# Current_Sense.net
KiCad netlist of a schematic drawn in Altium Designer
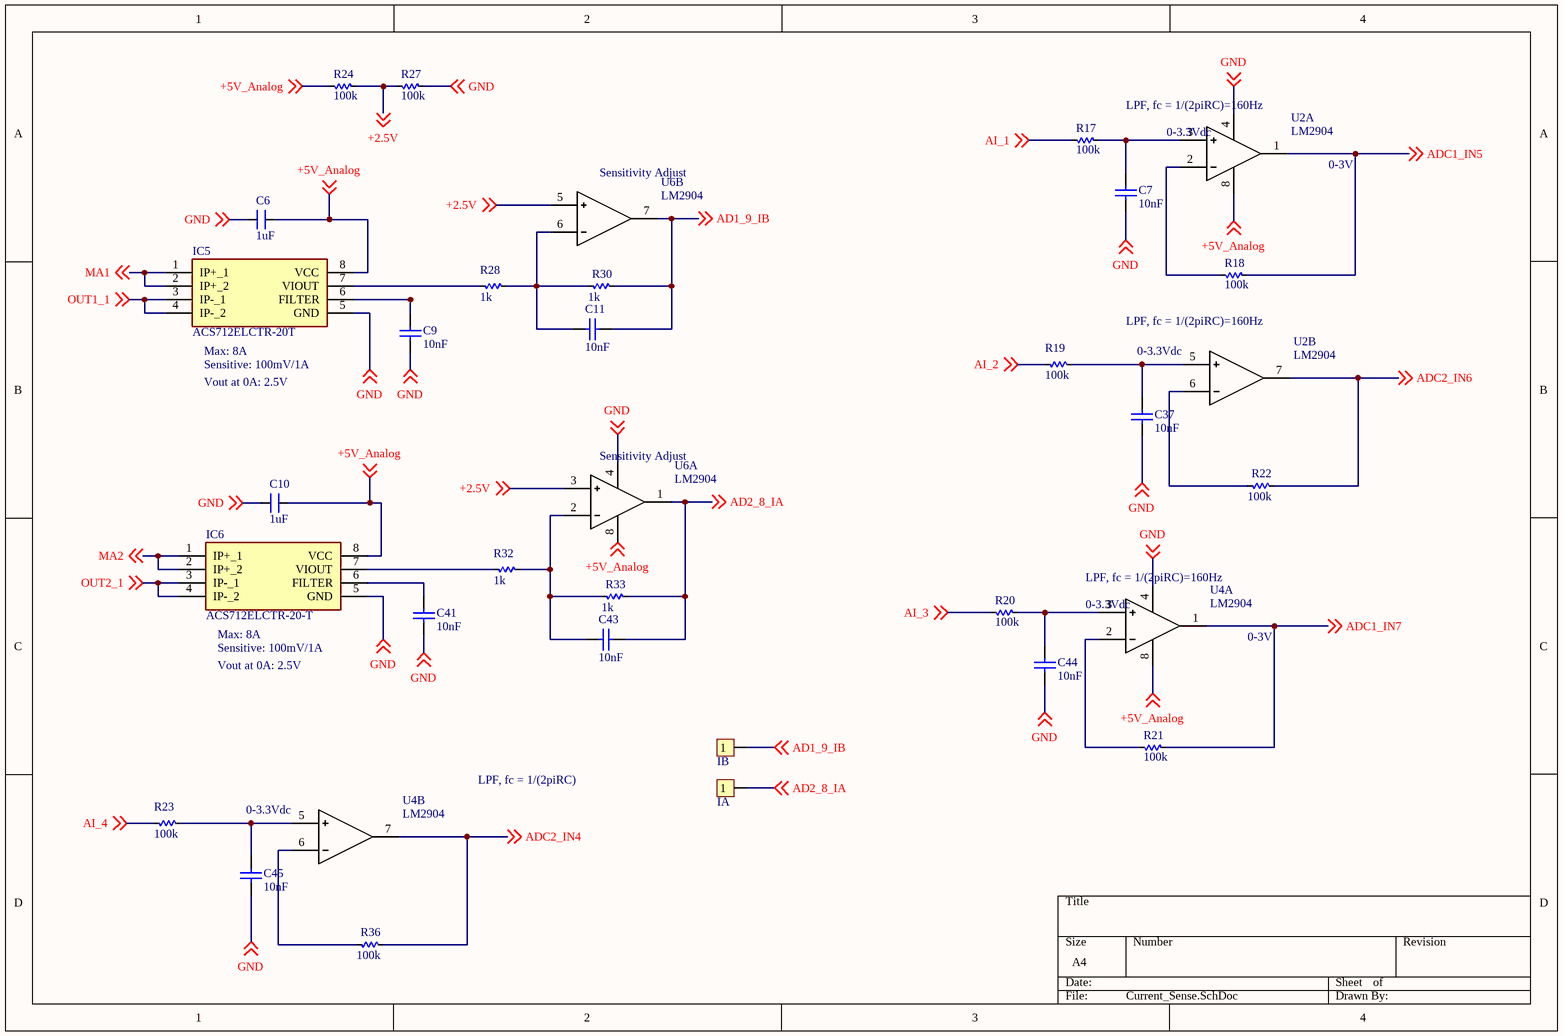
[diagram p0: Current_Sense.SchDoc]

(export (version "E")
  (design (tool "Eeschema 10.0.6"))
  (components
    (comp (ref "C6")
      (value "1uF")
      (footprint "Arduino_PLC_PCB:CM-0805 capacitor")
      (description "0805_SMD_20pF")
      (libsource (lib "Arduino_PLC_SchLib") (part "CN"))
    )
    (comp (ref "C7")
      (value "10nF")
      (footprint "tu 0603")
      (description "Dán")
      (libsource (lib "Tu dien") (part "Tu 0603 102 50V 10%"))
    )
    (comp (ref "C9")
      (value "10nF")
      (footprint "tu 0603")
      (description "Dán")
      (libsource (lib "Tu dien") (part "Tu 0603 102 50V 10%"))
    )
    (comp (ref "C10")
      (value "1uF")
      (footprint "Arduino_PLC_PCB:CM-0805 capacitor")
      (description "0805_SMD_20pF")
      (libsource (lib "Arduino_PLC_SchLib") (part "CN"))
    )
    (comp (ref "C11")
      (value "10nF")
      (footprint "tu 0603")
      (description "Dán")
      (libsource (lib "Tu dien") (part "Tu 0603 102 50V 10%"))
    )
    (comp (ref "C37")
      (value "10nF")
      (footprint "tu 0603")
      (description "Dán")
      (libsource (lib "Tu dien") (part "Tu 0603 102 50V 10%"))
    )
    (comp (ref "C41")
      (value "10nF")
      (footprint "tu 0603")
      (description "Dán")
      (libsource (lib "Tu dien") (part "Tu 0603 102 50V 10%"))
    )
    (comp (ref "C43")
      (value "10nF")
      (footprint "tu 0603")
      (description "Dán")
      (libsource (lib "Tu dien") (part "Tu 0603 102 50V 10%"))
    )
    (comp (ref "C44")
      (value "10nF")
      (footprint "tu 0603")
      (description "Dán")
      (libsource (lib "Tu dien") (part "Tu 0603 102 50V 10%"))
    )
    (comp (ref "C45")
      (value "10nF")
      (footprint "tu 0603")
      (description "Dán")
      (libsource (lib "Tu dien") (part "Tu 0603 102 50V 10%"))
    )
    (comp (ref "IA")
      (value "IA")
      (footprint "JP 1x1 DT")
      (description "Cắm")
      (libsource (lib "Jump") (part "JP 1x1 2.54 Duc Cong"))
    )
    (comp (ref "IB")
      (value "IB")
      (footprint "JP 1x1 DT")
      (description "Cắm")
      (libsource (lib "Jump") (part "JP 1x1 2.54 Duc Cong"))
    )
    (comp (ref "IC5")
      (value "ACS712ELCTR-20T")
      (footprint "SO8")
      (description "Integrated Circuit")
      (fields (field (name "MANUFACTURER_PART_NUMBER") "ACS712ELCTR-20A-T"))
      (libsource (lib "*") (part "ACS712ELCTR-20A-T"))
    )
    (comp (ref "IC6")
      (value "ACS712ELCTR-20-T")
      (footprint "SO8")
      (description "Integrated Circuit")
      (fields (field (name "MANUFACTURER_PART_NUMBER") "ACS712ELCTR-20A-T"))
      (libsource (lib "*") (part "ACS712ELCTR-20A-T"))
    )
    (comp (ref "R17")
      (value "100k")
      (footprint "RES-SMD-0603")
      (description "Resistor")
      (fields
        (field (name "MANUFACTURER") "Generic Components")
        (field (name "PUBLISHER") "Altium Hobart Technology Centre")
      )
      (libsource (lib "LIBRARY") (part "Res-SMD"))
    )
    (comp (ref "R18")
      (value "100k")
      (footprint "RES-SMD-0603")
      (description "Resistor")
      (fields
        (field (name "MANUFACTURER") "Generic Components")
        (field (name "PUBLISHER") "Altium Hobart Technology Centre")
      )
      (libsource (lib "LIBRARY") (part "Res-SMD"))
    )
    (comp (ref "R19")
      (value "100k")
      (footprint "RES-SMD-0603")
      (description "Resistor")
      (fields
        (field (name "MANUFACTURER") "Generic Components")
        (field (name "PUBLISHER") "Altium Hobart Technology Centre")
      )
      (libsource (lib "LIBRARY") (part "Res-SMD"))
    )
    (comp (ref "R20")
      (value "100k")
      (footprint "RES-SMD-0603")
      (description "Resistor")
      (fields
        (field (name "MANUFACTURER") "Generic Components")
        (field (name "PUBLISHER") "Altium Hobart Technology Centre")
      )
      (libsource (lib "LIBRARY") (part "Res-SMD"))
    )
    (comp (ref "R21")
      (value "100k")
      (footprint "RES-SMD-0603")
      (description "Resistor")
      (fields
        (field (name "MANUFACTURER") "Generic Components")
        (field (name "PUBLISHER") "Altium Hobart Technology Centre")
      )
      (libsource (lib "LIBRARY") (part "Res-SMD"))
    )
    (comp (ref "R22")
      (value "100k")
      (footprint "RES-SMD-0603")
      (description "Resistor")
      (fields
        (field (name "MANUFACTURER") "Generic Components")
        (field (name "PUBLISHER") "Altium Hobart Technology Centre")
      )
      (libsource (lib "LIBRARY") (part "Res-SMD"))
    )
    (comp (ref "R23")
      (value "100k")
      (footprint "RES-SMD-0603")
      (description "Resistor")
      (fields
        (field (name "MANUFACTURER") "Generic Components")
        (field (name "PUBLISHER") "Altium Hobart Technology Centre")
      )
      (libsource (lib "LIBRARY") (part "Res-SMD"))
    )
    (comp (ref "R24")
      (value "100k")
      (footprint "RES-SMD-0603")
      (description "Resistor")
      (fields
        (field (name "MANUFACTURER") "Generic Components")
        (field (name "PUBLISHER") "Altium Hobart Technology Centre")
      )
      (libsource (lib "LIBRARY") (part "Res-SMD"))
    )
    (comp (ref "R27")
      (value "100k")
      (footprint "RES-SMD-0603")
      (description "Resistor")
      (fields
        (field (name "MANUFACTURER") "Generic Components")
        (field (name "PUBLISHER") "Altium Hobart Technology Centre")
      )
      (libsource (lib "LIBRARY") (part "Res-SMD"))
    )
    (comp (ref "R28")
      (value "1k")
      (footprint "RES-SMD-0603")
      (description "Resistor")
      (fields
        (field (name "MANUFACTURER") "Generic Components")
        (field (name "PUBLISHER") "Altium Hobart Technology Centre")
      )
      (libsource (lib "LIBRARY") (part "Res-SMD"))
    )
    (comp (ref "R30")
      (value "1k")
      (footprint "RES-SMD-0603")
      (description "Resistor")
      (fields
        (field (name "MANUFACTURER") "Generic Components")
        (field (name "PUBLISHER") "Altium Hobart Technology Centre")
      )
      (libsource (lib "LIBRARY") (part "Res-SMD"))
    )
    (comp (ref "R32")
      (value "1k")
      (footprint "RES-SMD-0603")
      (description "Resistor")
      (fields
        (field (name "MANUFACTURER") "Generic Components")
        (field (name "PUBLISHER") "Altium Hobart Technology Centre")
      )
      (libsource (lib "LIBRARY") (part "Res-SMD"))
    )
    (comp (ref "R33")
      (value "1k")
      (footprint "RES-SMD-0603")
      (description "Resistor")
      (fields
        (field (name "MANUFACTURER") "Generic Components")
        (field (name "PUBLISHER") "Altium Hobart Technology Centre")
      )
      (libsource (lib "LIBRARY") (part "Res-SMD"))
    )
    (comp (ref "R36")
      (value "100k")
      (footprint "RES-SMD-0603")
      (description "Resistor")
      (fields
        (field (name "MANUFACTURER") "Generic Components")
        (field (name "PUBLISHER") "Altium Hobart Technology Centre")
      )
      (libsource (lib "LIBRARY") (part "Res-SMD"))
    )
    (comp (ref "U2")
      (value "LM2904")
      (footprint "SO8")
      (description "IC DUAL COMPARATOR")
      (libsource (lib "LIBRARY") (part "LM393-SPLIT"))
    )
    (comp (ref "U4")
      (value "LM2904")
      (footprint "SO8")
      (description "IC DUAL COMPARATOR")
      (libsource (lib "LIBRARY") (part "LM393-SPLIT"))
    )
    (comp (ref "U6")
      (value "LM2904")
      (footprint "SO8")
      (description "IC DUAL COMPARATOR")
      (libsource (lib "LIBRARY") (part "LM393-SPLIT"))
    )
  )
  (nets
    (net (code "1") (name "+2.5V") (class "Default")
      (node (ref "R24") (pin "1") (pinfunction "1_1") (pintype "passive"))
      (node (ref "R27") (pin "2") (pinfunction "2_2") (pintype "passive"))
      (node (ref "U6") (pin "3") (pintype "passive"))
      (node (ref "U6") (pin "5") (pintype "passive"))
    )
    (net (code "2") (name "+5V_Analog") (class "Default")
      (node (ref "C10") (pin "1") (pinfunction "1_1") (pintype "passive"))
      (node (ref "C6") (pin "1") (pinfunction "1_1") (pintype "passive"))
      (node (ref "IC5") (pin "8") (pinfunction "VCC_8") (pintype "passive"))
      (node (ref "IC6") (pin "8") (pinfunction "VCC_8") (pintype "passive"))
      (node (ref "R24") (pin "2") (pinfunction "2_2") (pintype "passive"))
      (node (ref "U2") (pin "8") (pinfunction "Vcc+_8") (pintype "passive"))
      (node (ref "U4") (pin "8") (pinfunction "Vcc+_8") (pintype "passive"))
      (node (ref "U6") (pin "8") (pinfunction "Vcc+_8") (pintype "passive"))
    )
    (net (code "3") (name "AD1_9_IB") (class "Default")
      (node (ref "C11") (pin "2") (pinfunction "2_2") (pintype "passive"))
      (node (ref "IB") (pin "1") (pinfunction "1_1") (pintype "passive"))
      (node (ref "R30") (pin "1") (pinfunction "1_1") (pintype "passive"))
      (node (ref "U6") (pin "7") (pintype "passive"))
    )
    (net (code "4") (name "AD2_8_IA") (class "Default")
      (node (ref "C43") (pin "2") (pinfunction "2_2") (pintype "passive"))
      (node (ref "IA") (pin "1") (pinfunction "1_1") (pintype "passive"))
      (node (ref "R33") (pin "1") (pinfunction "1_1") (pintype "passive"))
      (node (ref "U6") (pin "1") (pintype "passive"))
    )
    (net (code "5") (name "ADC1_IN5") (class "Default")
      (node (ref "R18") (pin "2") (pinfunction "2_2") (pintype "passive"))
      (node (ref "U2") (pin "1") (pintype "passive"))
    )
    (net (code "6") (name "ADC1_IN7") (class "Default")
      (node (ref "R21") (pin "2") (pinfunction "2_2") (pintype "passive"))
      (node (ref "U4") (pin "1") (pintype "passive"))
    )
    (net (code "7") (name "ADC2_IN4") (class "Default")
      (node (ref "R36") (pin "1") (pinfunction "1_1") (pintype "passive"))
      (node (ref "U4") (pin "7") (pintype "passive"))
    )
    (net (code "8") (name "ADC2_IN6") (class "Default")
      (node (ref "R22") (pin "1") (pinfunction "1_1") (pintype "passive"))
      (node (ref "U2") (pin "7") (pintype "passive"))
    )
    (net (code "9") (name "AI_1") (class "Default")
      (node (ref "R17") (pin "2") (pinfunction "2_2") (pintype "passive"))
    )
    (net (code "10") (name "AI_2") (class "Default")
      (node (ref "R19") (pin "1") (pinfunction "1_1") (pintype "passive"))
    )
    (net (code "11") (name "AI_3") (class "Default")
      (node (ref "R20") (pin "2") (pinfunction "2_2") (pintype "passive"))
    )
    (net (code "12") (name "AI_4") (class "Default")
      (node (ref "R23") (pin "1") (pinfunction "1_1") (pintype "passive"))
    )
    (net (code "13") (name "GND") (class "Default")
      (node (ref "C10") (pin "2") (pinfunction "2_2") (pintype "passive"))
      (node (ref "C37") (pin "2") (pinfunction "2_2") (pintype "passive"))
      (node (ref "C41") (pin "1") (pinfunction "1_1") (pintype "passive"))
      (node (ref "C44") (pin "1") (pinfunction "1_1") (pintype "passive"))
      (node (ref "C45") (pin "2") (pinfunction "2_2") (pintype "passive"))
      (node (ref "C6") (pin "2") (pinfunction "2_2") (pintype "passive"))
      (node (ref "C7") (pin "2") (pinfunction "2_2") (pintype "passive"))
      (node (ref "C9") (pin "2") (pinfunction "2_2") (pintype "passive"))
      (node (ref "IC5") (pin "5") (pinfunction "GND_5") (pintype "passive"))
      (node (ref "IC6") (pin "5") (pinfunction "GND_5") (pintype "passive"))
      (node (ref "R27") (pin "1") (pinfunction "1_1") (pintype "passive"))
      (node (ref "U2") (pin "4") (pinfunction "Vcc-_4") (pintype "passive"))
      (node (ref "U4") (pin "4") (pinfunction "Vcc-_4") (pintype "passive"))
      (node (ref "U6") (pin "4") (pinfunction "Vcc-_4") (pintype "passive"))
    )
    (net (code "14") (name "MA1") (class "Default")
      (node (ref "IC5") (pin "1") (pinfunction "IP+_1_1") (pintype "passive"))
      (node (ref "IC5") (pin "2") (pinfunction "IP+_2_2") (pintype "passive"))
    )
    (net (code "15") (name "MA2") (class "Default")
      (node (ref "IC6") (pin "1") (pinfunction "IP+_1_1") (pintype "passive"))
      (node (ref "IC6") (pin "2") (pinfunction "IP+_2_2") (pintype "passive"))
    )
    (net (code "16") (name "Net-(C7-Pad1)") (class "Default")
      (node (ref "C7") (pin "1") (pinfunction "1_1") (pintype "passive"))
      (node (ref "R17") (pin "1") (pinfunction "1_1") (pintype "passive"))
      (node (ref "U2") (pin "3") (pintype "passive"))
    )
    (net (code "17") (name "Net-(C11-Pad1)") (class "Default")
      (node (ref "C11") (pin "1") (pinfunction "1_1") (pintype "passive"))
      (node (ref "R28") (pin "2") (pinfunction "2_2") (pintype "passive"))
      (node (ref "R30") (pin "2") (pinfunction "2_2") (pintype "passive"))
      (node (ref "U6") (pin "6") (pintype "passive"))
    )
    (net (code "18") (name "Net-(C37-Pad1)") (class "Default")
      (node (ref "C37") (pin "1") (pinfunction "1_1") (pintype "passive"))
      (node (ref "R19") (pin "2") (pinfunction "2_2") (pintype "passive"))
      (node (ref "U2") (pin "5") (pintype "passive"))
    )
    (net (code "19") (name "Net-(C43-Pad1)") (class "Default")
      (node (ref "C43") (pin "1") (pinfunction "1_1") (pintype "passive"))
      (node (ref "R32") (pin "2") (pinfunction "2_2") (pintype "passive"))
      (node (ref "R33") (pin "2") (pinfunction "2_2") (pintype "passive"))
      (node (ref "U6") (pin "2") (pintype "passive"))
    )
    (net (code "20") (name "Net-(C44-Pad2)") (class "Default")
      (node (ref "C44") (pin "2") (pinfunction "2_2") (pintype "passive"))
      (node (ref "R20") (pin "1") (pinfunction "1_1") (pintype "passive"))
      (node (ref "U4") (pin "3") (pintype "passive"))
    )
    (net (code "21") (name "Net-(C45-Pad1)") (class "Default")
      (node (ref "C45") (pin "1") (pinfunction "1_1") (pintype "passive"))
      (node (ref "R23") (pin "2") (pinfunction "2_2") (pintype "passive"))
      (node (ref "U4") (pin "5") (pintype "passive"))
    )
    (net (code "22") (name "Net-(IC5-FILTER)") (class "Default")
      (node (ref "C9") (pin "1") (pinfunction "1_1") (pintype "passive"))
      (node (ref "IC5") (pin "6") (pinfunction "FILTER_6") (pintype "passive"))
    )
    (net (code "23") (name "Net-(IC5-VIOUT)") (class "Default")
      (node (ref "IC5") (pin "7") (pinfunction "VIOUT_7") (pintype "passive"))
      (node (ref "R28") (pin "1") (pinfunction "1_1") (pintype "passive"))
    )
    (net (code "24") (name "Net-(IC6-FILTER)") (class "Default")
      (node (ref "C41") (pin "2") (pinfunction "2_2") (pintype "passive"))
      (node (ref "IC6") (pin "6") (pinfunction "FILTER_6") (pintype "passive"))
    )
    (net (code "25") (name "Net-(IC6-VIOUT)") (class "Default")
      (node (ref "IC6") (pin "7") (pinfunction "VIOUT_7") (pintype "passive"))
      (node (ref "R32") (pin "1") (pinfunction "1_1") (pintype "passive"))
    )
    (net (code "26") (name "Net-(R18-Pad1)") (class "Default")
      (node (ref "R18") (pin "1") (pinfunction "1_1") (pintype "passive"))
      (node (ref "U2") (pin "2") (pintype "passive"))
    )
    (net (code "27") (name "Net-(R21-Pad1)") (class "Default")
      (node (ref "R21") (pin "1") (pinfunction "1_1") (pintype "passive"))
      (node (ref "U4") (pin "2") (pintype "passive"))
    )
    (net (code "28") (name "Net-(R22-Pad2)") (class "Default")
      (node (ref "R22") (pin "2") (pinfunction "2_2") (pintype "passive"))
      (node (ref "U2") (pin "6") (pintype "passive"))
    )
    (net (code "29") (name "Net-(R36-Pad2)") (class "Default")
      (node (ref "R36") (pin "2") (pinfunction "2_2") (pintype "passive"))
      (node (ref "U4") (pin "6") (pintype "passive"))
    )
    (net (code "30") (name "OUT1_1") (class "Default")
      (node (ref "IC5") (pin "3") (pinfunction "IP-_1_3") (pintype "passive"))
      (node (ref "IC5") (pin "4") (pinfunction "IP-_2_4") (pintype "passive"))
    )
    (net (code "31") (name "OUT2_1") (class "Default")
      (node (ref "IC6") (pin "3") (pinfunction "IP-_1_3") (pintype "passive"))
      (node (ref "IC6") (pin "4") (pinfunction "IP-_2_4") (pintype "passive"))
    )
  )
)
